# Rev1.net
KiCad netlist of a schematic drawn in EAGLE
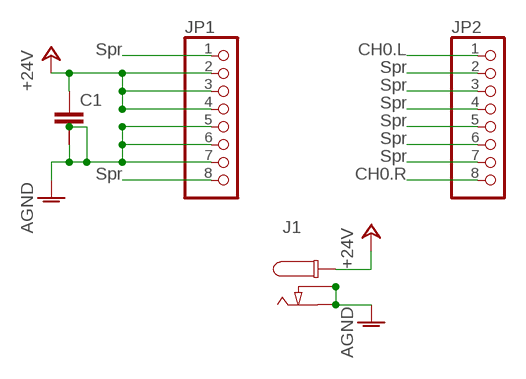
[diagram p0: schematic, sheet 1]

(export (version "E")
  (design (tool "Eeschema 10.0.6"))
  (components
    (comp (ref "C1")
      (value "C-2.5-5/6")
      (footprint "eagle-import:C2.5_5-6")
      (libsource (lib "eagle-import") (part "C-2.5-5/6"))
    )
    (comp (ref "J1")
      (value "CON_DC_M-DC_PTH")
      (footprint "eagle-import:DC_BARREL_JACK_PTH_2MM")
      (libsource (lib "eagle-import") (part "CON_DC_M-DC_PTH"))
    )
    (comp (ref "JP1")
      (value "PINHD-1X8")
      (footprint "eagle-import:1X08")
      (libsource (lib "eagle-import") (part "PINHD-1X8"))
    )
    (comp (ref "JP2")
      (value "PINHD-1X8")
      (footprint "eagle-import:1X08")
      (libsource (lib "eagle-import") (part "PINHD-1X8"))
    )
  )
  (nets
    (net (code "1") (name "+24V") (class "Default")
      (node (ref "C1") (pin "1") (pinfunction "1_1") (pintype "passive"))
      (node (ref "J1") (pin "P1") (pinfunction "P1_P1") (pintype "passive"))
      (node (ref "JP1") (pin "2") (pinfunction "2_2") (pintype "passive"))
      (node (ref "JP1") (pin "3") (pinfunction "3_3") (pintype "passive"))
      (node (ref "JP1") (pin "4") (pinfunction "4_4") (pintype "passive"))
    )
    (net (code "2") (name "AGND") (class "Default")
      (node (ref "C1") (pin "2") (pinfunction "2_2") (pintype "passive"))
      (node (ref "C1") (pin "3") (pinfunction "3_3") (pintype "passive"))
      (node (ref "J1") (pin "P2") (pinfunction "P3_P2") (pintype "passive"))
      (node (ref "J1") (pin "P3") (pinfunction "P2_P3") (pintype "passive"))
      (node (ref "JP1") (pin "5") (pinfunction "5_5") (pintype "passive"))
      (node (ref "JP1") (pin "6") (pinfunction "6_6") (pintype "passive"))
      (node (ref "JP1") (pin "7") (pinfunction "7_7") (pintype "passive"))
    )
    (net (code "3") (name "unconnected-(JP1-Pad1)") (class "Default")
      (node (ref "JP1") (pin "1") (pinfunction "1_1") (pintype "passive"))
    )
    (net (code "4") (name "unconnected-(JP1-Pad8)") (class "Default")
      (node (ref "JP1") (pin "8") (pinfunction "8_8") (pintype "passive"))
    )
    (net (code "5") (name "unconnected-(JP2-Pad1)") (class "Default")
      (node (ref "JP2") (pin "1") (pinfunction "1_1") (pintype "passive"))
    )
    (net (code "6") (name "unconnected-(JP2-Pad2)") (class "Default")
      (node (ref "JP2") (pin "2") (pinfunction "2_2") (pintype "passive"))
    )
    (net (code "7") (name "unconnected-(JP2-Pad3)") (class "Default")
      (node (ref "JP2") (pin "3") (pinfunction "3_3") (pintype "passive"))
    )
    (net (code "8") (name "unconnected-(JP2-Pad4)") (class "Default")
      (node (ref "JP2") (pin "4") (pinfunction "4_4") (pintype "passive"))
    )
    (net (code "9") (name "unconnected-(JP2-Pad5)") (class "Default")
      (node (ref "JP2") (pin "5") (pinfunction "5_5") (pintype "passive"))
    )
    (net (code "10") (name "unconnected-(JP2-Pad6)") (class "Default")
      (node (ref "JP2") (pin "6") (pinfunction "6_6") (pintype "passive"))
    )
    (net (code "11") (name "unconnected-(JP2-Pad7)") (class "Default")
      (node (ref "JP2") (pin "7") (pinfunction "7_7") (pintype "passive"))
    )
    (net (code "12") (name "unconnected-(JP2-Pad8)") (class "Default")
      (node (ref "JP2") (pin "8") (pinfunction "8_8") (pintype "passive"))
    )
  )
)
